# Power_Regulation.net
KiCad netlist of a schematic drawn in Altium Designer
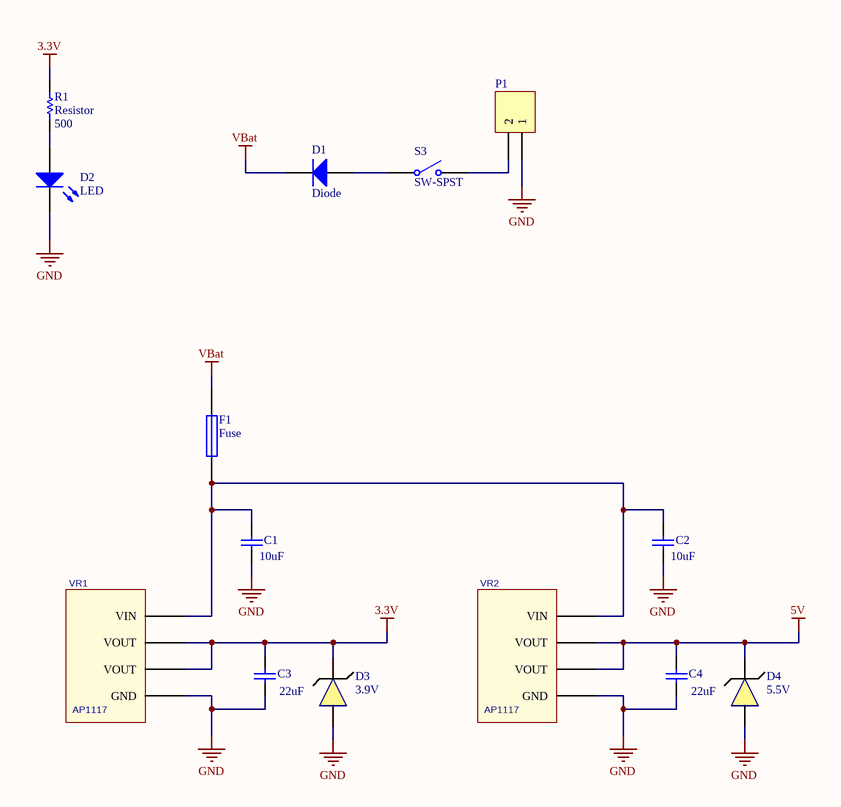
[diagram p0: Power_Regulation.SchDoc]

(export (version "E")
  (design (tool "Eeschema 10.0.6"))
  (components
    (comp (ref "C1")
      (value "10uF")
      (footprint "0805")
      (description "Capacitor")
      (fields (field (name "Comment") "Cap"))
      (libsource (lib "passives") (part "Cap"))
    )
    (comp (ref "C2")
      (value "10uF")
      (footprint "0805")
      (description "Capacitor")
      (fields (field (name "Comment") "Cap"))
      (libsource (lib "passives") (part "Cap"))
    )
    (comp (ref "C3")
      (value "22uF")
      (footprint "0805")
      (description "Capacitor")
      (fields (field (name "Comment") "Cap"))
      (libsource (lib "passives") (part "Cap"))
    )
    (comp (ref "C4")
      (value "22uF")
      (footprint "0805")
      (description "Capacitor")
      (fields (field (name "Comment") "Cap"))
      (libsource (lib "passives") (part "Cap"))
    )
    (comp (ref "D1")
      (value "Diode")
      (footprint "SMA")
      (description "Default Diode")
      (libsource (lib "diodes") (part "Diode"))
    )
    (comp (ref "D2")
      (value "LED")
      (footprint "0603")
      (fields
        (field (name "VENDOR PART NUMBER") "751-1203-ND")
        (field (name "MANUFACTURER") "Vishay")
        (field (name "MANUFACTURER PART NUMBER") "TSAL6100")
        (field (name "PUBLISHER") "Anthony Merlino")
      )
      (libsource (lib "passives") (part "LED"))
    )
    (comp (ref "D3") (value "3.9V") (footprint "DO-214AC") (libsource (lib "diodes") (part "Zener Diode")))
    (comp (ref "D4") (value "5.5V") (footprint "DO-214AC") (libsource (lib "diodes") (part "Zener Diode")))
    (comp (ref "F1")
      (value "Fuse")
      (footprint "0805")
      (fields (field (name "PUBLISHER") "Altium Limited"))
      (libsource (lib "passives") (part "Fuse"))
    )
    (comp (ref "P1")
      (value "Header 2")
      (footprint "HDR1X2")
      (description "Header, 2-Pin")
      (fields (field (name "PUBLISHER") "Altium Limited"))
      (libsource (lib "Miscellaneous Connectors") (part "Header 2"))
    )
    (comp (ref "R1")
      (value "Resistor")
      (footprint "0805")
      (fields (field (name "ALTIUM_VALUE") "500") (field (name "PUBLISHER") "Altium Limited"))
      (libsource (lib "passives") (part "Resistor"))
    )
    (comp (ref "S3")
      (value "SW-SPST")
      (footprint "SPST Switch")
      (description "Single-Pole, Single-Throw Switch")
      (fields (field (name "PUBLISHER") "Altium Limited"))
      (libsource (lib "switches") (part "SW-SPST"))
    )
    (comp (ref "VR1") (value "AP1117") (footprint "SOT-223") (libsource (lib "Devices") (part "AP1117")))
    (comp (ref "VR2") (value "AP1117") (footprint "SOT-223") (libsource (lib "Devices") (part "AP1117")))
  )
  (nets
    (net (code "1") (name "3.3V") (class "Default")
      (node (ref "C3") (pin "2") (pinfunction "2_2") (pintype "passive"))
      (node (ref "D3") (pin "1") (pintype "passive"))
      (node (ref "R1") (pin "2") (pinfunction "2_2") (pintype "passive"))
      (node (ref "VR1") (pin "2") (pinfunction "VOUT_2") (pintype "passive"))
      (node (ref "VR1") (pin "4") (pinfunction "VOUT_4") (pintype "passive"))
    )
    (net (code "2") (name "5V") (class "Default")
      (node (ref "C4") (pin "2") (pinfunction "2_2") (pintype "passive"))
      (node (ref "D4") (pin "1") (pintype "passive"))
      (node (ref "VR2") (pin "2") (pinfunction "VOUT_2") (pintype "passive"))
      (node (ref "VR2") (pin "4") (pinfunction "VOUT_4") (pintype "passive"))
    )
    (net (code "3") (name "GND") (class "Default")
      (node (ref "C1") (pin "1") (pinfunction "1_1") (pintype "passive"))
      (node (ref "C2") (pin "1") (pinfunction "1_1") (pintype "passive"))
      (node (ref "C3") (pin "1") (pinfunction "1_1") (pintype "passive"))
      (node (ref "C4") (pin "1") (pinfunction "1_1") (pintype "passive"))
      (node (ref "D2") (pin "2") (pinfunction "K_2") (pintype "passive"))
      (node (ref "D3") (pin "2") (pintype "passive"))
      (node (ref "D4") (pin "2") (pintype "passive"))
      (node (ref "P1") (pin "1") (pinfunction "1_1") (pintype "passive"))
      (node (ref "VR1") (pin "1") (pinfunction "GND_1") (pintype "passive"))
      (node (ref "VR2") (pin "1") (pinfunction "GND_1") (pintype "passive"))
    )
    (net (code "4") (name "Net-(D1-A)") (class "Default")
      (node (ref "D1") (pin "1") (pinfunction "A_1") (pintype "passive"))
      (node (ref "S3") (pin "1") (pinfunction "COMMON_1") (pintype "passive"))
    )
    (net (code "5") (name "Net-(D2-A)") (class "Default")
      (node (ref "D2") (pin "1") (pinfunction "A_1") (pintype "passive"))
      (node (ref "R1") (pin "1") (pinfunction "1_1") (pintype "passive"))
    )
    (net (code "6") (name "Net-(S3-NO)") (class "Default")
      (node (ref "P1") (pin "2") (pinfunction "2_2") (pintype "passive"))
      (node (ref "S3") (pin "2") (pinfunction "NO_2") (pintype "passive"))
    )
    (net (code "7") (name "Net-(VR1-VIN)") (class "Default")
      (node (ref "C1") (pin "2") (pinfunction "2_2") (pintype "passive"))
      (node (ref "C2") (pin "2") (pinfunction "2_2") (pintype "passive"))
      (node (ref "F1") (pin "1") (pinfunction "1_1") (pintype "passive"))
      (node (ref "VR1") (pin "3") (pinfunction "VIN_3") (pintype "passive"))
      (node (ref "VR2") (pin "3") (pinfunction "VIN_3") (pintype "passive"))
    )
    (net (code "8") (name "VBat") (class "Default")
      (node (ref "D1") (pin "2") (pinfunction "K_2") (pintype "passive"))
      (node (ref "F1") (pin "2") (pinfunction "2_2") (pintype "passive"))
    )
  )
)
